# UI_mon.net
KiCad netlist of a schematic drawn in Altium Designer
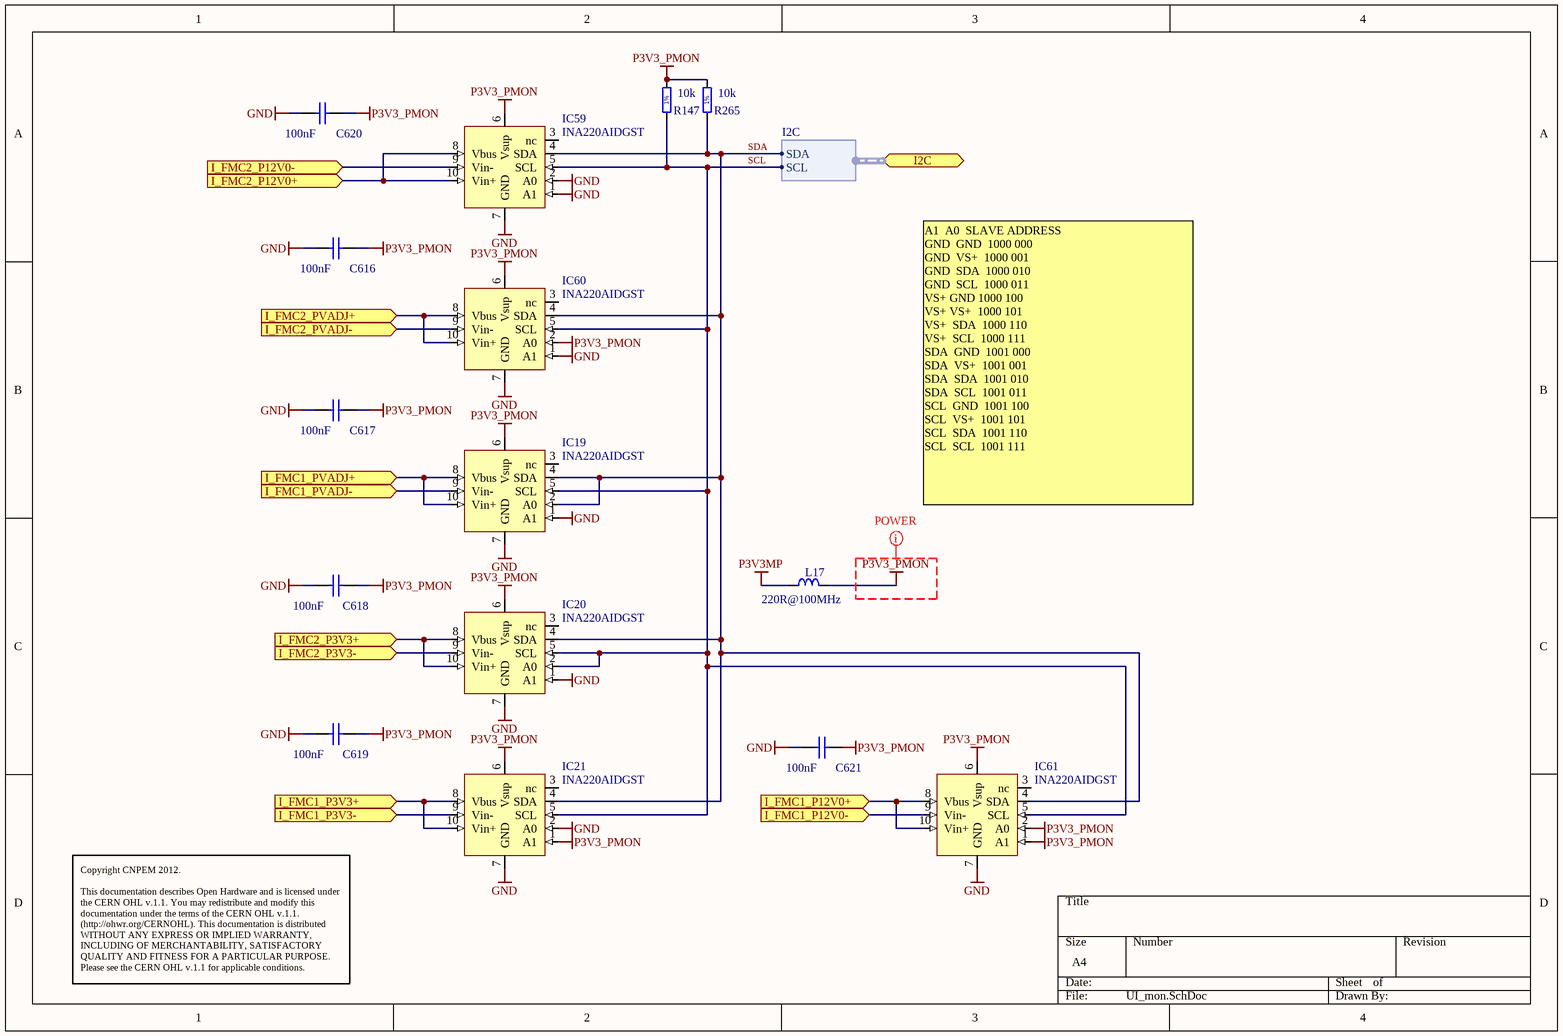
[diagram p0: UI_mon.SchDoc]

(export (version "E")
  (design (tool "Eeschema 10.0.6"))
  (components
    (comp (ref "C616")
      (value "100nF")
      (footprint "CAPC0603X33N")
      (description "Non-polarised capacitor")
      (fields
        (field (name "PART NUMBER") "CC0201_100NF_6.3V_10%_X5R")
        (field (name "VOLTAGE") "6.3V")
        (field (name "AUTHOR") "CERN DEM JLC")
      )
      (libsource (lib "Capacitors") (part "Capacitor - non polarized"))
    )
    (comp (ref "C617")
      (value "100nF")
      (footprint "CAPC0603X33N")
      (description "Non-polarised capacitor")
      (fields
        (field (name "PART NUMBER") "CC0201_100NF_6.3V_10%_X5R")
        (field (name "VOLTAGE") "6.3V")
        (field (name "AUTHOR") "CERN DEM JLC")
      )
      (libsource (lib "Capacitors") (part "Capacitor - non polarized"))
    )
    (comp (ref "C618")
      (value "100nF")
      (footprint "CAPC0603X33N")
      (description "Non-polarised capacitor")
      (fields
        (field (name "PART NUMBER") "CC0201_100NF_6.3V_10%_X5R")
        (field (name "VOLTAGE") "6.3V")
        (field (name "AUTHOR") "CERN DEM JLC")
      )
      (libsource (lib "Capacitors") (part "Capacitor - non polarized"))
    )
    (comp (ref "C619")
      (value "100nF")
      (footprint "CAPC0603X33N")
      (description "Non-polarised capacitor")
      (fields
        (field (name "PART NUMBER") "CC0201_100NF_6.3V_10%_X5R")
        (field (name "VOLTAGE") "6.3V")
        (field (name "AUTHOR") "CERN DEM JLC")
      )
      (libsource (lib "Capacitors") (part "Capacitor - non polarized"))
    )
    (comp (ref "C620")
      (value "100nF")
      (footprint "CAPC0603X33N")
      (description "Non-polarised capacitor")
      (fields
        (field (name "PART NUMBER") "CC0201_100NF_6.3V_10%_X5R")
        (field (name "VOLTAGE") "6.3V")
        (field (name "AUTHOR") "CERN DEM JLC")
      )
      (libsource (lib "Capacitors") (part "Capacitor - non polarized"))
    )
    (comp (ref "C621")
      (value "100nF")
      (footprint "CAPC0603X33N")
      (description "Non-polarised capacitor")
      (fields
        (field (name "PART NUMBER") "CC0201_100NF_6.3V_10%_X5R")
        (field (name "VOLTAGE") "6.3V")
        (field (name "AUTHOR") "CERN DEM JLC")
      )
      (libsource (lib "Capacitors") (part "Capacitor - non polarized"))
    )
    (comp (ref "IC19")
      (value "INA220AIDGST")
      (footprint "msop10")
      (description "CURRENT/POWER MONITOR with Two-Wire Interface")
      (libsource (lib "LIBRARY_SCH") (part "ADC_INA220"))
    )
    (comp (ref "IC20")
      (value "INA220AIDGST")
      (footprint "msop10")
      (description "CURRENT/POWER MONITOR with Two-Wire Interface")
      (libsource (lib "LIBRARY_SCH") (part "ADC_INA220"))
    )
    (comp (ref "IC21")
      (value "INA220AIDGST")
      (footprint "msop10")
      (description "CURRENT/POWER MONITOR with Two-Wire Interface")
      (libsource (lib "LIBRARY_SCH") (part "ADC_INA220"))
    )
    (comp (ref "IC59")
      (value "INA220AIDGST")
      (footprint "msop10")
      (description "CURRENT/POWER MONITOR with Two-Wire Interface")
      (libsource (lib "LIBRARY_SCH") (part "ADC_INA220"))
    )
    (comp (ref "IC60")
      (value "INA220AIDGST")
      (footprint "msop10")
      (description "CURRENT/POWER MONITOR with Two-Wire Interface")
      (libsource (lib "LIBRARY_SCH") (part "ADC_INA220"))
    )
    (comp (ref "IC61")
      (value "INA220AIDGST")
      (footprint "msop10")
      (description "CURRENT/POWER MONITOR with Two-Wire Interface")
      (libsource (lib "LIBRARY_SCH") (part "ADC_INA220"))
    )
    (comp (ref "L17")
      (value "220R@100MHz")
      (footprint "INDC2012X105N")
      (description "Inductor")
      (fields
        (field (name "PART NUMBER") "IND0805_MURATA_BLM21PG221SN1D")
        (field (name "POWER") "2A")
        (field (name "AUTHOR") "CERN DEM JLC")
      )
      (libsource (lib "Inductors & Transformers") (part "Inductor"))
    )
    (comp (ref "R147")
      (value "10k")
      (footprint "RESC1005X40N")
      (description "Resistor - 1%")
      (fields
        (field (name "PART NUMBER") "R0402_10K_1%_0.0625W_100PPM")
        (field (name "POWER") "0.0625W")
        (field (name "AUTHOR") "CERN DEM JLC")
      )
      (libsource (lib "Resistors") (part "Resistor - 1%"))
    )
    (comp (ref "R265")
      (value "10k")
      (footprint "RESC1005X40N")
      (description "Resistor - 1%")
      (fields
        (field (name "PART NUMBER") "R0402_10K_1%_0.0625W_100PPM")
        (field (name "POWER") "0.0625W")
        (field (name "AUTHOR") "CERN DEM JLC")
      )
      (libsource (lib "Resistors") (part "Resistor - 1%"))
    )
  )
  (nets
    (net (code "2") (name "/I_FMC1_P3V3+") (class "Default")
      (node (ref "IC21") (pin "10") (pinfunction "Vin+_10") (pintype "input"))
      (node (ref "IC21") (pin "8") (pinfunction "Vbus_8") (pintype "input"))
    )
    (net (code "3") (name "/I_FMC1_P3V3-") (class "Default")
      (node (ref "IC21") (pin "9") (pinfunction "Vin-_9") (pintype "input"))
    )
    (net (code "4") (name "/I_FMC1_P12V0+") (class "Default")
      (node (ref "IC61") (pin "10") (pinfunction "Vin+_10") (pintype "input"))
      (node (ref "IC61") (pin "8") (pinfunction "Vbus_8") (pintype "input"))
    )
    (net (code "5") (name "/I_FMC1_P12V0-") (class "Default")
      (node (ref "IC61") (pin "9") (pinfunction "Vin-_9") (pintype "input"))
    )
    (net (code "6") (name "/I_FMC1_PVADJ+") (class "Default")
      (node (ref "IC19") (pin "10") (pinfunction "Vin+_10") (pintype "input"))
      (node (ref "IC19") (pin "8") (pinfunction "Vbus_8") (pintype "input"))
    )
    (net (code "7") (name "/I_FMC1_PVADJ-") (class "Default")
      (node (ref "IC19") (pin "9") (pinfunction "Vin-_9") (pintype "input"))
    )
    (net (code "8") (name "/I_FMC2_P3V3+") (class "Default")
      (node (ref "IC20") (pin "10") (pinfunction "Vin+_10") (pintype "input"))
      (node (ref "IC20") (pin "8") (pinfunction "Vbus_8") (pintype "input"))
    )
    (net (code "9") (name "/I_FMC2_P3V3-") (class "Default")
      (node (ref "IC20") (pin "9") (pinfunction "Vin-_9") (pintype "input"))
    )
    (net (code "10") (name "/I_FMC2_P12V0+") (class "Default")
      (node (ref "IC59") (pin "10") (pinfunction "Vin+_10") (pintype "input"))
      (node (ref "IC59") (pin "8") (pinfunction "Vbus_8") (pintype "input"))
    )
    (net (code "11") (name "/I_FMC2_P12V0-") (class "Default")
      (node (ref "IC59") (pin "9") (pinfunction "Vin-_9") (pintype "input"))
    )
    (net (code "12") (name "/I_FMC2_PVADJ+") (class "Default")
      (node (ref "IC60") (pin "10") (pinfunction "Vin+_10") (pintype "input"))
      (node (ref "IC60") (pin "8") (pinfunction "Vbus_8") (pintype "input"))
    )
    (net (code "13") (name "/I_FMC2_PVADJ-") (class "Default")
      (node (ref "IC60") (pin "9") (pinfunction "Vin-_9") (pintype "input"))
    )
    (net (code "14") (name "/SCL") (class "Default")
      (node (ref "IC19") (pin "5") (pinfunction "SCL_5") (pintype "input"))
      (node (ref "IC20") (pin "2") (pinfunction "A0_2") (pintype "input"))
      (node (ref "IC20") (pin "5") (pinfunction "SCL_5") (pintype "input"))
      (node (ref "IC21") (pin "5") (pinfunction "SCL_5") (pintype "input"))
      (node (ref "IC59") (pin "5") (pinfunction "SCL_5") (pintype "input"))
      (node (ref "IC60") (pin "5") (pinfunction "SCL_5") (pintype "input"))
      (node (ref "IC61") (pin "5") (pinfunction "SCL_5") (pintype "input"))
      (node (ref "R147") (pin "1") (pinfunction "1_1") (pintype "passive"))
    )
    (net (code "15") (name "/SDA") (class "Default")
      (node (ref "IC19") (pin "2") (pinfunction "A0_2") (pintype "input"))
      (node (ref "IC19") (pin "4") (pinfunction "SDA_4") (pintype "bidirectional"))
      (node (ref "IC20") (pin "4") (pinfunction "SDA_4") (pintype "bidirectional"))
      (node (ref "IC21") (pin "4") (pinfunction "SDA_4") (pintype "bidirectional"))
      (node (ref "IC59") (pin "4") (pinfunction "SDA_4") (pintype "bidirectional"))
      (node (ref "IC60") (pin "4") (pinfunction "SDA_4") (pintype "bidirectional"))
      (node (ref "IC61") (pin "4") (pinfunction "SDA_4") (pintype "bidirectional"))
      (node (ref "R265") (pin "1") (pinfunction "1_1") (pintype "passive"))
    )
    (net (code "17") (name "GND") (class "Default")
      (node (ref "C616") (pin "2") (pinfunction "2_2") (pintype "passive"))
      (node (ref "C617") (pin "2") (pinfunction "2_2") (pintype "passive"))
      (node (ref "C618") (pin "2") (pinfunction "2_2") (pintype "passive"))
      (node (ref "C619") (pin "2") (pinfunction "2_2") (pintype "passive"))
      (node (ref "C620") (pin "2") (pinfunction "2_2") (pintype "passive"))
      (node (ref "C621") (pin "2") (pinfunction "2_2") (pintype "passive"))
      (node (ref "IC19") (pin "1") (pinfunction "A1_1") (pintype "input"))
      (node (ref "IC19") (pin "7") (pinfunction "GND_7") (pintype "power_in"))
      (node (ref "IC20") (pin "1") (pinfunction "A1_1") (pintype "input"))
      (node (ref "IC20") (pin "7") (pinfunction "GND_7") (pintype "power_in"))
      (node (ref "IC21") (pin "2") (pinfunction "A0_2") (pintype "input"))
      (node (ref "IC21") (pin "7") (pinfunction "GND_7") (pintype "power_in"))
      (node (ref "IC59") (pin "1") (pinfunction "A1_1") (pintype "input"))
      (node (ref "IC59") (pin "2") (pinfunction "A0_2") (pintype "input"))
      (node (ref "IC59") (pin "7") (pinfunction "GND_7") (pintype "power_in"))
      (node (ref "IC60") (pin "1") (pinfunction "A1_1") (pintype "input"))
      (node (ref "IC60") (pin "7") (pinfunction "GND_7") (pintype "power_in"))
      (node (ref "IC61") (pin "7") (pinfunction "GND_7") (pintype "power_in"))
    )
    (net (code "18") (name "P3V3MP") (class "Default")
      (node (ref "L17") (pin "1") (pinfunction "1_1") (pintype "passive"))
    )
    (net (code "19") (name "P3V3_PMON") (class "Default")
      (node (ref "C616") (pin "1") (pinfunction "1_1") (pintype "passive"))
      (node (ref "C617") (pin "1") (pinfunction "1_1") (pintype "passive"))
      (node (ref "C618") (pin "1") (pinfunction "1_1") (pintype "passive"))
      (node (ref "C619") (pin "1") (pinfunction "1_1") (pintype "passive"))
      (node (ref "C620") (pin "1") (pinfunction "1_1") (pintype "passive"))
      (node (ref "C621") (pin "1") (pinfunction "1_1") (pintype "passive"))
      (node (ref "IC19") (pin "6") (pinfunction "Vsup_6") (pintype "power_in"))
      (node (ref "IC20") (pin "6") (pinfunction "Vsup_6") (pintype "power_in"))
      (node (ref "IC21") (pin "1") (pinfunction "A1_1") (pintype "input"))
      (node (ref "IC21") (pin "6") (pinfunction "Vsup_6") (pintype "power_in"))
      (node (ref "IC59") (pin "6") (pinfunction "Vsup_6") (pintype "power_in"))
      (node (ref "IC60") (pin "2") (pinfunction "A0_2") (pintype "input"))
      (node (ref "IC60") (pin "6") (pinfunction "Vsup_6") (pintype "power_in"))
      (node (ref "IC61") (pin "1") (pinfunction "A1_1") (pintype "input"))
      (node (ref "IC61") (pin "2") (pinfunction "A0_2") (pintype "input"))
      (node (ref "IC61") (pin "6") (pinfunction "Vsup_6") (pintype "power_in"))
      (node (ref "L17") (pin "2") (pinfunction "2_2") (pintype "passive"))
      (node (ref "R147") (pin "2") (pinfunction "2_2") (pintype "passive"))
      (node (ref "R265") (pin "2") (pinfunction "2_2") (pintype "passive"))
    )
    (net (code "20") (name "unconnected-(IC19-nc-Pad3)") (class "Default")
      (node (ref "IC19") (pin "3") (pinfunction "nc_3") (pintype "passive"))
    )
    (net (code "21") (name "unconnected-(IC20-nc-Pad3)") (class "Default")
      (node (ref "IC20") (pin "3") (pinfunction "nc_3") (pintype "passive"))
    )
    (net (code "22") (name "unconnected-(IC21-nc-Pad3)") (class "Default")
      (node (ref "IC21") (pin "3") (pinfunction "nc_3") (pintype "passive"))
    )
    (net (code "23") (name "unconnected-(IC59-nc-Pad3)") (class "Default")
      (node (ref "IC59") (pin "3") (pinfunction "nc_3") (pintype "passive"))
    )
    (net (code "24") (name "unconnected-(IC60-nc-Pad3)") (class "Default")
      (node (ref "IC60") (pin "3") (pinfunction "nc_3") (pintype "passive"))
    )
    (net (code "25") (name "unconnected-(IC61-nc-Pad3)") (class "Default")
      (node (ref "IC61") (pin "3") (pinfunction "nc_3") (pintype "passive"))
    )
  )
)
